# Sheet1.net
KiCad netlist of a schematic drawn in Altium Designer
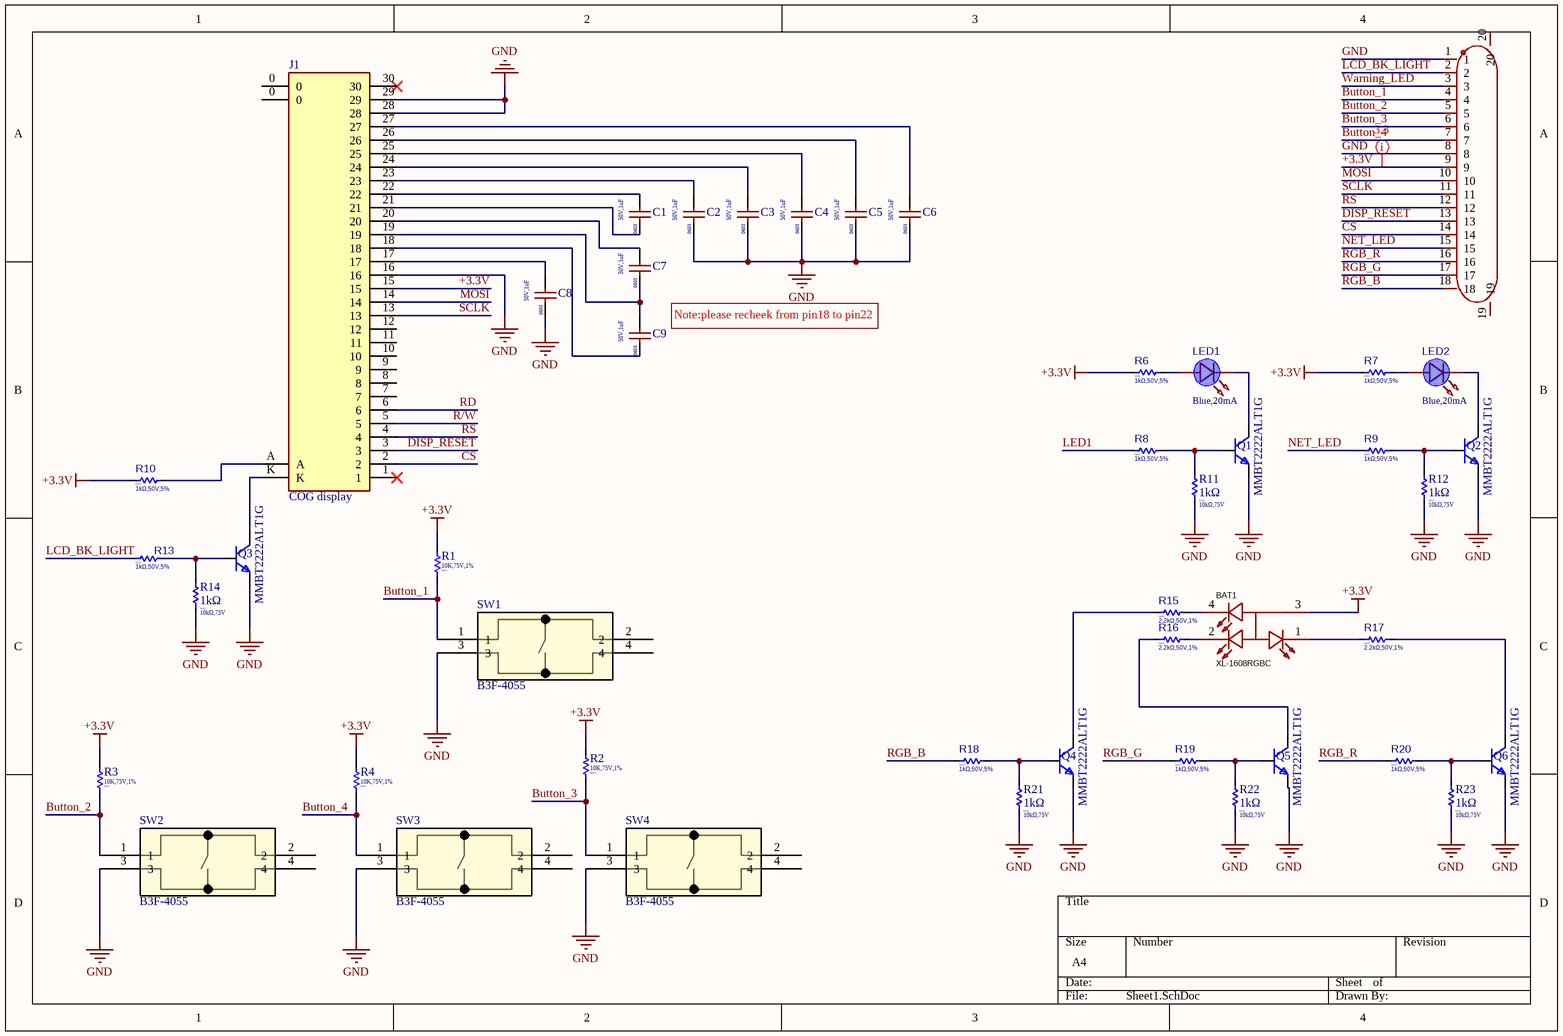
[diagram p0: Sheet1.SchDoc]

(export (version "E")
  (design (tool "Eeschema 10.0.6"))
  (components
    (comp (ref "BAT1")
      (value "XL-1608RGBC")
      (footprint "LED RGB 0603")
      (description "0603 RGB LEDs ROHS")
      (fields (field (name "MANUFACTURER") "XINGLIGHT"))
      (libsource (lib "LED") (part "XL-1608RGBC"))
    )
    (comp (ref "C1")
      (value "50V,1uF")
      (footprint "C0603")
      (description "50V 1uF X7R ±10% 0603 Multilayer Ceramic Capacitors MLCC - SMD/SMT ROHS")
      (fields
        (field (name "MANUFACTURER") "FH")
        (field (name "MPN") "0603B105K500NT")
        (field (name "PACKAGE") "0603")
      )
      (libsource (lib "RCL") (part "0603B105K500NT"))
    )
    (comp (ref "C2")
      (value "50V,1uF")
      (footprint "C0603")
      (description "50V 1uF X7R ±10% 0603 Multilayer Ceramic Capacitors MLCC - SMD/SMT ROHS")
      (fields
        (field (name "MANUFACTURER") "FH")
        (field (name "MPN") "0603B105K500NT")
        (field (name "PACKAGE") "0603")
      )
      (libsource (lib "RCL") (part "0603B105K500NT"))
    )
    (comp (ref "C3")
      (value "50V,1uF")
      (footprint "C0603")
      (description "50V 1uF X7R ±10% 0603 Multilayer Ceramic Capacitors MLCC - SMD/SMT ROHS")
      (fields
        (field (name "MANUFACTURER") "FH")
        (field (name "MPN") "0603B105K500NT")
        (field (name "PACKAGE") "0603")
      )
      (libsource (lib "RCL") (part "0603B105K500NT"))
    )
    (comp (ref "C4")
      (value "50V,1uF")
      (footprint "C0603")
      (description "50V 1uF X7R ±10% 0603 Multilayer Ceramic Capacitors MLCC - SMD/SMT ROHS")
      (fields
        (field (name "MANUFACTURER") "FH")
        (field (name "MPN") "0603B105K500NT")
        (field (name "PACKAGE") "0603")
      )
      (libsource (lib "RCL") (part "0603B105K500NT"))
    )
    (comp (ref "C5")
      (value "50V,1uF")
      (footprint "C0603")
      (description "50V 1uF X7R ±10% 0603 Multilayer Ceramic Capacitors MLCC - SMD/SMT ROHS")
      (fields
        (field (name "MANUFACTURER") "FH")
        (field (name "MPN") "0603B105K500NT")
        (field (name "PACKAGE") "0603")
      )
      (libsource (lib "RCL") (part "0603B105K500NT"))
    )
    (comp (ref "C6")
      (value "50V,1uF")
      (footprint "C0603")
      (description "50V 1uF X7R ±10% 0603 Multilayer Ceramic Capacitors MLCC - SMD/SMT ROHS")
      (fields
        (field (name "MANUFACTURER") "FH")
        (field (name "MPN") "0603B105K500NT")
        (field (name "PACKAGE") "0603")
      )
      (libsource (lib "RCL") (part "0603B105K500NT"))
    )
    (comp (ref "C7")
      (value "50V,1uF")
      (footprint "C0603")
      (description "50V 1uF X7R ±10% 0603 Multilayer Ceramic Capacitors MLCC - SMD/SMT ROHS")
      (fields
        (field (name "MANUFACTURER") "FH")
        (field (name "MPN") "0603B105K500NT")
        (field (name "PACKAGE") "0603")
      )
      (libsource (lib "RCL") (part "0603B105K500NT"))
    )
    (comp (ref "C8")
      (value "50V,1uF")
      (footprint "C0603")
      (description "50V 1uF X7R ±10% 0603 Multilayer Ceramic Capacitors MLCC - SMD/SMT ROHS")
      (fields
        (field (name "MANUFACTURER") "FH")
        (field (name "MPN") "0603B105K500NT")
        (field (name "PACKAGE") "0603")
      )
      (libsource (lib "RCL") (part "0603B105K500NT"))
    )
    (comp (ref "C9")
      (value "50V,1uF")
      (footprint "C0603")
      (description "50V 1uF X7R ±10% 0603 Multilayer Ceramic Capacitors MLCC - SMD/SMT ROHS")
      (fields
        (field (name "MANUFACTURER") "FH")
        (field (name "MPN") "0603B105K500NT")
        (field (name "PACKAGE") "0603")
      )
      (libsource (lib "RCL") (part "0603B105K500NT"))
    )
    (comp (ref "FPC1")
      (value "FPC-05F-18PH20")
      (footprint "FPC-SMD_18P-P0.50_horizontal")
      (fields (field (name "MANUFACTURER") "XUNPU"))
      (libsource (lib "connector_button") (part "FPC-05F-18PH20"))
    )
    (comp (ref "J1")
      (value "COG display")
      (footprint "COG")
      (description "FPC CONNECTOR")
      (fields (field (name "MANUFACTURER") "XFCN"))
      (libsource (lib "Display") (part "COG display"))
    )
    (comp (ref "LED1")
      (value "Blue,20mA")
      (footprint "LED 0402")
      (fields (field (name "MANUFACTURER") "TOGIALED") (field (name "MPN") "TJ-S1005CL4T5ALC6B-A5"))
      (libsource (lib "LED") (part "TJ-S1005CL4T5ALC6B-A5"))
    )
    (comp (ref "LED2")
      (value "Blue,20mA")
      (footprint "LED 0402")
      (fields (field (name "MANUFACTURER") "TOGIALED") (field (name "MPN") "TJ-S1005CL4T5ALC6B-A5"))
      (libsource (lib "LED") (part "TJ-S1005CL4T5ALC6B-A5"))
    )
    (comp (ref "Q1")
      (value "MMBT2222ALT1G")
      (footprint "SOT-23")
      (description "Bipolar (BJT) Transistor NPN 40 V 600 mA 300MHz 225 mW Surface Mount SOT-23-3 (TO-236)")
      (fields (field (name "MANUFACTURER") "ON Semiconductor"))
      (libsource (lib "MOS_TRAN") (part "MMBT2222ALT1G"))
    )
    (comp (ref "Q2")
      (value "MMBT2222ALT1G")
      (footprint "SOT-23")
      (description "Bipolar (BJT) Transistor NPN 40 V 600 mA 300MHz 225 mW Surface Mount SOT-23-3 (TO-236)")
      (fields (field (name "MANUFACTURER") "ON Semiconductor"))
      (libsource (lib "MOS_TRAN") (part "MMBT2222ALT1G"))
    )
    (comp (ref "Q3")
      (value "MMBT2222ALT1G")
      (footprint "SOT-23")
      (description "Bipolar (BJT) Transistor NPN 40 V 600 mA 300MHz 225 mW Surface Mount SOT-23-3 (TO-236)")
      (fields (field (name "MANUFACTURER") "ON Semiconductor"))
      (libsource (lib "MOS_TRAN") (part "MMBT2222ALT1G"))
    )
    (comp (ref "Q4")
      (value "MMBT2222ALT1G")
      (footprint "SOT-23")
      (description "Bipolar (BJT) Transistor NPN 40 V 600 mA 300MHz 225 mW Surface Mount SOT-23-3 (TO-236)")
      (fields (field (name "MANUFACTURER") "ON Semiconductor"))
      (libsource (lib "MOS_TRAN") (part "MMBT2222ALT1G"))
    )
    (comp (ref "Q5")
      (value "MMBT2222ALT1G")
      (footprint "SOT-23")
      (description "Bipolar (BJT) Transistor NPN 40 V 600 mA 300MHz 225 mW Surface Mount SOT-23-3 (TO-236)")
      (fields (field (name "MANUFACTURER") "ON Semiconductor"))
      (libsource (lib "MOS_TRAN") (part "MMBT2222ALT1G"))
    )
    (comp (ref "Q6")
      (value "MMBT2222ALT1G")
      (footprint "SOT-23")
      (description "Bipolar (BJT) Transistor NPN 40 V 600 mA 300MHz 225 mW Surface Mount SOT-23-3 (TO-236)")
      (fields (field (name "MANUFACTURER") "ON Semiconductor"))
      (libsource (lib "MOS_TRAN") (part "MMBT2222ALT1G"))
    )
    (comp (ref "R1")
      (value "10K,75V,1%")
      (footprint "R0603")
      (description "100mW Thick Film Resistors ±100ppm/℃ ±1% 10kΩ 0603 Chip Resistor - Surface Mount ROHS")
      (fields
        (field (name "MPN") "0603WAF1002T5E")
        (field (name "MANUFACTURER") "UNI-ROYAL(Uniroyal Elec)")
        (field (name "PACKAGE") "0603")
      )
      (libsource (lib "RCL") (part "0603WAF1002T5E"))
    )
    (comp (ref "R2")
      (value "10K,75V,1%")
      (footprint "R0603")
      (description "100mW Thick Film Resistors ±100ppm/℃ ±1% 10kΩ 0603 Chip Resistor - Surface Mount ROHS")
      (fields
        (field (name "MPN") "0603WAF1002T5E")
        (field (name "MANUFACTURER") "UNI-ROYAL(Uniroyal Elec)")
        (field (name "PACKAGE") "0603")
      )
      (libsource (lib "RCL") (part "0603WAF1002T5E"))
    )
    (comp (ref "R3")
      (value "10K,75V,1%")
      (footprint "R0603")
      (description "100mW Thick Film Resistors ±100ppm/℃ ±1% 10kΩ 0603 Chip Resistor - Surface Mount ROHS")
      (fields
        (field (name "MPN") "0603WAF1002T5E")
        (field (name "MANUFACTURER") "UNI-ROYAL(Uniroyal Elec)")
        (field (name "PACKAGE") "0603")
      )
      (libsource (lib "RCL") (part "0603WAF1002T5E"))
    )
    (comp (ref "R4")
      (value "10K,75V,1%")
      (footprint "R0603")
      (description "100mW Thick Film Resistors ±100ppm/℃ ±1% 10kΩ 0603 Chip Resistor - Surface Mount ROHS")
      (fields
        (field (name "MPN") "0603WAF1002T5E")
        (field (name "MANUFACTURER") "UNI-ROYAL(Uniroyal Elec)")
        (field (name "PACKAGE") "0603")
      )
      (libsource (lib "RCL") (part "0603WAF1002T5E"))
    )
    (comp (ref "R6")
      (value "1kΩ,50V,5%")
      (footprint "R0402")
      (description "125mW Thick Film Resistors 50V ±200ppm/℃ ±5% 1kΩ 0402 Chip Resistor - Surface Mount ROHS")
      (fields
        (field (name "MPN") "SR0402JR-7W1KL")
        (field (name "MANUFACTURER") "YAGEO")
        (field (name "PACKAGE") "0402")
      )
      (libsource (lib "RCL") (part "SR0402JR-7W1KL"))
    )
    (comp (ref "R7")
      (value "1kΩ,50V,5%")
      (footprint "R0402")
      (description "125mW Thick Film Resistors 50V ±200ppm/℃ ±5% 1kΩ 0402 Chip Resistor - Surface Mount ROHS")
      (fields
        (field (name "MPN") "SR0402JR-7W1KL")
        (field (name "MANUFACTURER") "YAGEO")
        (field (name "PACKAGE") "0402")
      )
      (libsource (lib "RCL") (part "SR0402JR-7W1KL"))
    )
    (comp (ref "R8")
      (value "1kΩ,50V,5%")
      (footprint "R0402")
      (description "125mW Thick Film Resistors 50V ±200ppm/℃ ±5% 1kΩ 0402 Chip Resistor - Surface Mount ROHS")
      (fields
        (field (name "MPN") "SR0402JR-7W1KL")
        (field (name "MANUFACTURER") "YAGEO")
        (field (name "PACKAGE") "0402")
      )
      (libsource (lib "RCL") (part "SR0402JR-7W1KL"))
    )
    (comp (ref "R9")
      (value "1kΩ,50V,5%")
      (footprint "R0402")
      (description "125mW Thick Film Resistors 50V ±200ppm/℃ ±5% 1kΩ 0402 Chip Resistor - Surface Mount ROHS")
      (fields
        (field (name "MPN") "SR0402JR-7W1KL")
        (field (name "MANUFACTURER") "YAGEO")
        (field (name "PACKAGE") "0402")
      )
      (libsource (lib "RCL") (part "SR0402JR-7W1KL"))
    )
    (comp (ref "R10")
      (value "1kΩ,50V,5%")
      (footprint "R0402")
      (description "125mW Thick Film Resistors 50V ±200ppm/℃ ±5% 1kΩ 0402 Chip Resistor - Surface Mount ROHS")
      (fields
        (field (name "MPN") "SR0402JR-7W1KL")
        (field (name "MANUFACTURER") "YAGEO")
        (field (name "PACKAGE") "0402")
      )
      (libsource (lib "RCL") (part "SR0402JR-7W1KL"))
    )
    (comp (ref "R11")
      (value "1kΩ")
      (footprint "R0402")
      (description "62.5mW Thick Film Resistors ±100ppm/℃ ±1% 1kΩ 0402 Chip Resistor - Surface Mount ROHS")
      (fields
        (field (name "MANUFACTURER") "UNI-ROYAL(Uniroyal Elec)")
        (field (name "MPN") "0603WAF1002T5E")
        (field (name "PACKAGE") "0402")
        (field (name "ALTIUM_VALUE") "10kΩ,75V")
      )
      (libsource (lib "RCL") (part "0402WGF1001TCE"))
    )
    (comp (ref "R12")
      (value "1kΩ")
      (footprint "R0402")
      (description "62.5mW Thick Film Resistors ±100ppm/℃ ±1% 1kΩ 0402 Chip Resistor - Surface Mount ROHS")
      (fields
        (field (name "MANUFACTURER") "UNI-ROYAL(Uniroyal Elec)")
        (field (name "MPN") "0603WAF1002T5E")
        (field (name "PACKAGE") "0402")
        (field (name "ALTIUM_VALUE") "10kΩ,75V")
      )
      (libsource (lib "RCL") (part "0402WGF1001TCE"))
    )
    (comp (ref "R13")
      (value "1kΩ,50V,5%")
      (footprint "R0402")
      (description "125mW Thick Film Resistors 50V ±200ppm/℃ ±5% 1kΩ 0402 Chip Resistor - Surface Mount ROHS")
      (fields
        (field (name "MPN") "SR0402JR-7W1KL")
        (field (name "MANUFACTURER") "YAGEO")
        (field (name "PACKAGE") "0402")
      )
      (libsource (lib "RCL") (part "SR0402JR-7W1KL"))
    )
    (comp (ref "R14")
      (value "1kΩ")
      (footprint "R0402")
      (description "62.5mW Thick Film Resistors ±100ppm/℃ ±1% 1kΩ 0402 Chip Resistor - Surface Mount ROHS")
      (fields
        (field (name "MANUFACTURER") "UNI-ROYAL(Uniroyal Elec)")
        (field (name "MPN") "0603WAF1002T5E")
        (field (name "PACKAGE") "0402")
        (field (name "ALTIUM_VALUE") "10kΩ,75V")
      )
      (libsource (lib "RCL") (part "0402WGF1001TCE"))
    )
    (comp (ref "R15")
      (value "2.2kΩ,50V,1%")
      (footprint "R0402")
      (description "62.5mW Thick Film Resistors 50V ±100ppm/℃ ±1% 2.2kΩ 0402 Chip Resistor - Surface Mount ROHS")
      (fields
        (field (name "MPN") "RC0402FR-072K2L")
        (field (name "MANUFACTURER") "YAGEO")
        (field (name "PACKAGE") "0402")
      )
      (libsource (lib "RCL") (part "RC0402FR-072K2L"))
    )
    (comp (ref "R16")
      (value "2.2kΩ,50V,1%")
      (footprint "R0402")
      (description "62.5mW Thick Film Resistors 50V ±100ppm/℃ ±1% 2.2kΩ 0402 Chip Resistor - Surface Mount ROHS")
      (fields
        (field (name "MPN") "RC0402FR-072K2L")
        (field (name "MANUFACTURER") "YAGEO")
        (field (name "PACKAGE") "0402")
      )
      (libsource (lib "RCL") (part "RC0402FR-072K2L"))
    )
    (comp (ref "R17")
      (value "2.2kΩ,50V,1%")
      (footprint "R0402")
      (description "62.5mW Thick Film Resistors 50V ±100ppm/℃ ±1% 2.2kΩ 0402 Chip Resistor - Surface Mount ROHS")
      (fields
        (field (name "MPN") "RC0402FR-072K2L")
        (field (name "MANUFACTURER") "YAGEO")
        (field (name "PACKAGE") "0402")
      )
      (libsource (lib "RCL") (part "RC0402FR-072K2L"))
    )
    (comp (ref "R18")
      (value "1kΩ,50V,5%")
      (footprint "R0402")
      (description "125mW Thick Film Resistors 50V ±200ppm/℃ ±5% 1kΩ 0402 Chip Resistor - Surface Mount ROHS")
      (fields
        (field (name "MPN") "SR0402JR-7W1KL")
        (field (name "MANUFACTURER") "YAGEO")
        (field (name "PACKAGE") "0402")
      )
      (libsource (lib "RCL") (part "SR0402JR-7W1KL"))
    )
    (comp (ref "R19")
      (value "1kΩ,50V,5%")
      (footprint "R0402")
      (description "125mW Thick Film Resistors 50V ±200ppm/℃ ±5% 1kΩ 0402 Chip Resistor - Surface Mount ROHS")
      (fields
        (field (name "MPN") "SR0402JR-7W1KL")
        (field (name "MANUFACTURER") "YAGEO")
        (field (name "PACKAGE") "0402")
      )
      (libsource (lib "RCL") (part "SR0402JR-7W1KL"))
    )
    (comp (ref "R20")
      (value "1kΩ,50V,5%")
      (footprint "R0402")
      (description "125mW Thick Film Resistors 50V ±200ppm/℃ ±5% 1kΩ 0402 Chip Resistor - Surface Mount ROHS")
      (fields
        (field (name "MPN") "SR0402JR-7W1KL")
        (field (name "MANUFACTURER") "YAGEO")
        (field (name "PACKAGE") "0402")
      )
      (libsource (lib "RCL") (part "SR0402JR-7W1KL"))
    )
    (comp (ref "R21")
      (value "1kΩ")
      (footprint "R0402")
      (description "62.5mW Thick Film Resistors ±100ppm/℃ ±1% 1kΩ 0402 Chip Resistor - Surface Mount ROHS")
      (fields
        (field (name "MANUFACTURER") "UNI-ROYAL(Uniroyal Elec)")
        (field (name "MPN") "0603WAF1002T5E")
        (field (name "PACKAGE") "0402")
        (field (name "ALTIUM_VALUE") "10kΩ,75V")
      )
      (libsource (lib "RCL") (part "0402WGF1001TCE"))
    )
    (comp (ref "R22")
      (value "1kΩ")
      (footprint "R0402")
      (description "62.5mW Thick Film Resistors ±100ppm/℃ ±1% 1kΩ 0402 Chip Resistor - Surface Mount ROHS")
      (fields
        (field (name "MANUFACTURER") "UNI-ROYAL(Uniroyal Elec)")
        (field (name "MPN") "0603WAF1002T5E")
        (field (name "PACKAGE") "0402")
        (field (name "ALTIUM_VALUE") "10kΩ,75V")
      )
      (libsource (lib "RCL") (part "0402WGF1001TCE"))
    )
    (comp (ref "R23")
      (value "1kΩ")
      (footprint "R0402")
      (description "62.5mW Thick Film Resistors ±100ppm/℃ ±1% 1kΩ 0402 Chip Resistor - Surface Mount ROHS")
      (fields
        (field (name "MANUFACTURER") "UNI-ROYAL(Uniroyal Elec)")
        (field (name "MPN") "0603WAF1002T5E")
        (field (name "PACKAGE") "0402")
        (field (name "ALTIUM_VALUE") "10kΩ,75V")
      )
      (libsource (lib "RCL") (part "0402WGF1001TCE"))
    )
    (comp (ref "SW1")
      (value "B3F-4055")
      (footprint "SW_B3F-4050_OMR")
      (description "Tactile Switch SPST-NO Top Actuated Through Hole")
      (libsource (lib "connector_button") (part "B3F-4055"))
    )
    (comp (ref "SW2")
      (value "B3F-4055")
      (footprint "SW_B3F-4050_OMR")
      (description "Tactile Switch SPST-NO Top Actuated Through Hole")
      (libsource (lib "connector_button") (part "B3F-4055"))
    )
    (comp (ref "SW3")
      (value "B3F-4055")
      (footprint "SW_B3F-4050_OMR")
      (description "Tactile Switch SPST-NO Top Actuated Through Hole")
      (libsource (lib "connector_button") (part "B3F-4055"))
    )
    (comp (ref "SW4")
      (value "B3F-4055")
      (footprint "SW_B3F-4050_OMR")
      (description "Tactile Switch SPST-NO Top Actuated Through Hole")
      (libsource (lib "connector_button") (part "B3F-4055"))
    )
  )
  (nets
    (net (code "1") (name "+3.3V") (class "Default")
      (node (ref "BAT1") (pin "3") (pinfunction "com_3") (pintype "passive"))
      (node (ref "FPC1") (pin "9") (pinfunction "9_9") (pintype "passive"))
      (node (ref "J1") (pin "15") (pinfunction "15_15") (pintype "passive"))
      (node (ref "R1") (pin "2") (pinfunction "2_2") (pintype "passive"))
      (node (ref "R10") (pin "1") (pinfunction "1_1") (pintype "passive"))
      (node (ref "R2") (pin "2") (pinfunction "2_2") (pintype "passive"))
      (node (ref "R3") (pin "2") (pinfunction "2_2") (pintype "passive"))
      (node (ref "R4") (pin "2") (pinfunction "2_2") (pintype "passive"))
      (node (ref "R6") (pin "1") (pinfunction "1_1") (pintype "passive"))
      (node (ref "R7") (pin "1") (pinfunction "1_1") (pintype "passive"))
    )
    (net (code "2") (name "/Button_1") (class "Default")
      (node (ref "FPC1") (pin "4") (pinfunction "4_4") (pintype "passive"))
      (node (ref "R1") (pin "1") (pinfunction "1_1") (pintype "passive"))
      (node (ref "SW1") (pin "1") (pinfunction "1_1") (pintype "passive"))
    )
    (net (code "3") (name "/Button_2") (class "Default")
      (node (ref "FPC1") (pin "5") (pinfunction "5_5") (pintype "passive"))
      (node (ref "R3") (pin "1") (pinfunction "1_1") (pintype "passive"))
      (node (ref "SW2") (pin "1") (pinfunction "1_1") (pintype "passive"))
    )
    (net (code "4") (name "/Button_3") (class "Default")
      (node (ref "FPC1") (pin "6") (pinfunction "6_6") (pintype "passive"))
      (node (ref "R2") (pin "1") (pinfunction "1_1") (pintype "passive"))
      (node (ref "SW4") (pin "1") (pinfunction "1_1") (pintype "passive"))
    )
    (net (code "5") (name "/Button_4") (class "Default")
      (node (ref "FPC1") (pin "7") (pinfunction "7_7") (pintype "passive"))
      (node (ref "R4") (pin "1") (pinfunction "1_1") (pintype "passive"))
      (node (ref "SW3") (pin "1") (pinfunction "1_1") (pintype "passive"))
    )
    (net (code "6") (name "/CS") (class "Default")
      (node (ref "FPC1") (pin "14") (pinfunction "14_14") (pintype "passive"))
      (node (ref "J1") (pin "2") (pinfunction "2_2") (pintype "passive"))
    )
    (net (code "7") (name "/DISP_RESET") (class "Default")
      (node (ref "FPC1") (pin "13") (pinfunction "13_13") (pintype "passive"))
      (node (ref "J1") (pin "3") (pinfunction "3_3") (pintype "passive"))
    )
    (net (code "8") (name "/LCD_BK_LIGHT") (class "Default")
      (node (ref "FPC1") (pin "2") (pinfunction "2_2") (pintype "passive"))
      (node (ref "R13") (pin "1") (pinfunction "1_1") (pintype "passive"))
    )
    (net (code "9") (name "/LED1") (class "Default")
      (node (ref "R8") (pin "1") (pinfunction "1_1") (pintype "passive"))
    )
    (net (code "10") (name "/MOSI") (class "Default")
      (node (ref "FPC1") (pin "10") (pinfunction "10_10") (pintype "passive"))
      (node (ref "J1") (pin "14") (pinfunction "14_14") (pintype "passive"))
    )
    (net (code "11") (name "/NET_LED") (class "Default")
      (node (ref "FPC1") (pin "15") (pinfunction "15_15") (pintype "passive"))
      (node (ref "R9") (pin "1") (pinfunction "1_1") (pintype "passive"))
    )
    (net (code "12") (name "/RD") (class "Default")
      (node (ref "J1") (pin "6") (pinfunction "6_6") (pintype "passive"))
    )
    (net (code "13") (name "/RGB_B") (class "Default")
      (node (ref "FPC1") (pin "18") (pinfunction "18_18") (pintype "passive"))
      (node (ref "R18") (pin "1") (pinfunction "1_1") (pintype "passive"))
    )
    (net (code "14") (name "/RGB_G") (class "Default")
      (node (ref "FPC1") (pin "17") (pinfunction "17_17") (pintype "passive"))
      (node (ref "R19") (pin "1") (pinfunction "1_1") (pintype "passive"))
    )
    (net (code "15") (name "/RGB_R") (class "Default")
      (node (ref "FPC1") (pin "16") (pinfunction "16_16") (pintype "passive"))
      (node (ref "R20") (pin "1") (pinfunction "1_1") (pintype "passive"))
    )
    (net (code "16") (name "/RS") (class "Default")
      (node (ref "FPC1") (pin "12") (pinfunction "12_12") (pintype "passive"))
      (node (ref "J1") (pin "4") (pinfunction "4_4") (pintype "passive"))
    )
    (net (code "17") (name "/R{slash}W") (class "Default")
      (node (ref "J1") (pin "5") (pinfunction "5_5") (pintype "passive"))
    )
    (net (code "18") (name "/SCLK") (class "Default")
      (node (ref "FPC1") (pin "11") (pinfunction "11_11") (pintype "passive"))
      (node (ref "J1") (pin "13") (pinfunction "13_13") (pintype "passive"))
    )
    (net (code "19") (name "/Warning_LED") (class "Default")
      (node (ref "FPC1") (pin "3") (pinfunction "3_3") (pintype "passive"))
    )
    (net (code "20") (name "GND") (class "Default")
      (node (ref "C2") (pin "1") (pinfunction "1_1") (pintype "passive"))
      (node (ref "C3") (pin "1") (pinfunction "1_1") (pintype "passive"))
      (node (ref "C4") (pin "1") (pinfunction "1_1") (pintype "passive"))
      (node (ref "C5") (pin "1") (pinfunction "1_1") (pintype "passive"))
      (node (ref "C6") (pin "1") (pinfunction "1_1") (pintype "passive"))
      (node (ref "C8") (pin "1") (pinfunction "1_1") (pintype "passive"))
      (node (ref "FPC1") (pin "1") (pinfunction "1_1") (pintype "passive"))
      (node (ref "FPC1") (pin "8") (pinfunction "8_8") (pintype "passive"))
      (node (ref "J1") (pin "16") (pinfunction "16_16") (pintype "passive"))
      (node (ref "J1") (pin "28") (pinfunction "28_28") (pintype "passive"))
      (node (ref "J1") (pin "29") (pinfunction "29_29") (pintype "passive"))
      (node (ref "Q1") (pin "2") (pinfunction "2_2") (pintype "passive"))
      (node (ref "Q2") (pin "2") (pinfunction "2_2") (pintype "passive"))
      (node (ref "Q3") (pin "2") (pinfunction "2_2") (pintype "passive"))
      (node (ref "Q4") (pin "2") (pinfunction "2_2") (pintype "passive"))
      (node (ref "Q5") (pin "2") (pinfunction "2_2") (pintype "passive"))
      (node (ref "Q6") (pin "2") (pinfunction "2_2") (pintype "passive"))
      (node (ref "R11") (pin "1") (pinfunction "1_1") (pintype "passive"))
      (node (ref "R12") (pin "1") (pinfunction "1_1") (pintype "passive"))
      (node (ref "R14") (pin "1") (pinfunction "1_1") (pintype "passive"))
      (node (ref "R21") (pin "1") (pinfunction "1_1") (pintype "passive"))
      (node (ref "R22") (pin "1") (pinfunction "1_1") (pintype "passive"))
      (node (ref "R23") (pin "1") (pinfunction "1_1") (pintype "passive"))
      (node (ref "SW1") (pin "3") (pinfunction "3_3") (pintype "passive"))
      (node (ref "SW2") (pin "3") (pinfunction "3_3") (pintype "passive"))
      (node (ref "SW3") (pin "3") (pinfunction "3_3") (pintype "passive"))
      (node (ref "SW4") (pin "3") (pinfunction "3_3") (pintype "passive"))
    )
    (net (code "21") (name "Net-(BAT1-Pad1)") (class "Default")
      (node (ref "BAT1") (pin "1") (pinfunction "1_1") (pintype "passive"))
      (node (ref "R17") (pin "1") (pinfunction "1_1") (pintype "passive"))
    )
    (net (code "22") (name "Net-(BAT1-Pad2)") (class "Default")
      (node (ref "BAT1") (pin "2") (pinfunction "2_2") (pintype "passive"))
      (node (ref "R16") (pin "1") (pinfunction "1_1") (pintype "passive"))
    )
    (net (code "23") (name "Net-(BAT1-Pad4)") (class "Default")
      (node (ref "BAT1") (pin "4") (pinfunction "4_4") (pintype "passive"))
      (node (ref "R15") (pin "1") (pinfunction "1_1") (pintype "passive"))
    )
    (net (code "24") (name "Net-(C1-Pad1)") (class "Default")
      (node (ref "C1") (pin "1") (pinfunction "1_1") (pintype "passive"))
      (node (ref "J1") (pin "21") (pinfunction "21_21") (pintype "passive"))
    )
    (net (code "25") (name "Net-(C1-Pad2)") (class "Default")
      (node (ref "C1") (pin "2") (pinfunction "2_2") (pintype "passive"))
      (node (ref "J1") (pin "22") (pinfunction "22_22") (pintype "passive"))
    )
    (net (code "26") (name "Net-(C2-Pad2)") (class "Default")
      (node (ref "C2") (pin "2") (pinfunction "2_2") (pintype "passive"))
      (node (ref "J1") (pin "23") (pinfunction "23_23") (pintype "passive"))
    )
    (net (code "27") (name "Net-(C3-Pad2)") (class "Default")
      (node (ref "C3") (pin "2") (pinfunction "2_2") (pintype "passive"))
      (node (ref "J1") (pin "24") (pinfunction "24_24") (pintype "passive"))
    )
    (net (code "28") (name "Net-(C4-Pad2)") (class "Default")
      (node (ref "C4") (pin "2") (pinfunction "2_2") (pintype "passive"))
      (node (ref "J1") (pin "25") (pinfunction "25_25") (pintype "passive"))
    )
    (net (code "29") (name "Net-(C5-Pad2)") (class "Default")
      (node (ref "C5") (pin "2") (pinfunction "2_2") (pintype "passive"))
      (node (ref "J1") (pin "26") (pinfunction "26_26") (pintype "passive"))
    )
    (net (code "30") (name "Net-(C6-Pad2)") (class "Default")
      (node (ref "C6") (pin "2") (pinfunction "2_2") (pintype "passive"))
      (node (ref "J1") (pin "27") (pinfunction "27_27") (pintype "passive"))
    )
    (net (code "31") (name "Net-(C7-Pad1)") (class "Default")
      (node (ref "C7") (pin "1") (pinfunction "1_1") (pintype "passive"))
      (node (ref "C9") (pin "2") (pinfunction "2_2") (pintype "passive"))
      (node (ref "J1") (pin "19") (pinfunction "19_19") (pintype "passive"))
    )
    (net (code "32") (name "Net-(C7-Pad2)") (class "Default")
      (node (ref "C7") (pin "2") (pinfunction "2_2") (pintype "passive"))
      (node (ref "J1") (pin "20") (pinfunction "20_20") (pintype "passive"))
    )
    (net (code "33") (name "Net-(C8-Pad2)") (class "Default")
      (node (ref "C8") (pin "2") (pinfunction "2_2") (pintype "passive"))
      (node (ref "J1") (pin "17") (pinfunction "17_17") (pintype "passive"))
    )
    (net (code "34") (name "Net-(C9-Pad1)") (class "Default")
      (node (ref "C9") (pin "1") (pinfunction "1_1") (pintype "passive"))
      (node (ref "J1") (pin "18") (pinfunction "18_18") (pintype "passive"))
    )
    (net (code "35") (name "Net-(J1-PadA)") (class "Default")
      (node (ref "J1") (pin "A") (pinfunction "A_A") (pintype "passive"))
      (node (ref "R10") (pin "2") (pinfunction "2_2") (pintype "passive"))
    )
    (net (code "36") (name "Net-(J1-PadK)") (class "Default")
      (node (ref "J1") (pin "K") (pinfunction "K_K") (pintype "passive"))
      (node (ref "Q3") (pin "3") (pinfunction "3_3") (pintype "passive"))
    )
    (net (code "37") (name "Net-(LED1-A)") (class "Default")
      (node (ref "LED1") (pin "2") (pinfunction "A_2") (pintype "passive"))
      (node (ref "R6") (pin "2") (pinfunction "2_2") (pintype "passive"))
    )
    (net (code "38") (name "Net-(LED1-K)") (class "Default")
      (node (ref "LED1") (pin "1") (pinfunction "K_1") (pintype "passive"))
      (node (ref "Q1") (pin "3") (pinfunction "3_3") (pintype "passive"))
    )
    (net (code "39") (name "Net-(LED2-A)") (class "Default")
      (node (ref "LED2") (pin "2") (pinfunction "A_2") (pintype "passive"))
      (node (ref "R7") (pin "2") (pinfunction "2_2") (pintype "passive"))
    )
    (net (code "40") (name "Net-(LED2-K)") (class "Default")
      (node (ref "LED2") (pin "1") (pinfunction "K_1") (pintype "passive"))
      (node (ref "Q2") (pin "3") (pinfunction "3_3") (pintype "passive"))
    )
    (net (code "41") (name "Net-(Q1-Pad1)") (class "Default")
      (node (ref "Q1") (pin "1") (pinfunction "1_1") (pintype "passive"))
      (node (ref "R11") (pin "2") (pinfunction "2_2") (pintype "passive"))
      (node (ref "R8") (pin "2") (pinfunction "2_2") (pintype "passive"))
    )
    (net (code "42") (name "Net-(Q2-Pad1)") (class "Default")
      (node (ref "Q2") (pin "1") (pinfunction "1_1") (pintype "passive"))
      (node (ref "R12") (pin "2") (pinfunction "2_2") (pintype "passive"))
      (node (ref "R9") (pin "2") (pinfunction "2_2") (pintype "passive"))
    )
    (net (code "43") (name "Net-(Q3-Pad1)") (class "Default")
      (node (ref "Q3") (pin "1") (pinfunction "1_1") (pintype "passive"))
      (node (ref "R13") (pin "2") (pinfunction "2_2") (pintype "passive"))
      (node (ref "R14") (pin "2") (pinfunction "2_2") (pintype "passive"))
    )
    (net (code "44") (name "Net-(Q4-Pad1)") (class "Default")
      (node (ref "Q4") (pin "1") (pinfunction "1_1") (pintype "passive"))
      (node (ref "R18") (pin "2") (pinfunction "2_2") (pintype "passive"))
      (node (ref "R21") (pin "2") (pinfunction "2_2") (pintype "passive"))
    )
    (net (code "45") (name "Net-(Q4-Pad3)") (class "Default")
      (node (ref "Q4") (pin "3") (pinfunction "3_3") (pintype "passive"))
      (node (ref "R15") (pin "2") (pinfunction "2_2") (pintype "passive"))
    )
    (net (code "46") (name "Net-(Q5-Pad1)") (class "Default")
      (node (ref "Q5") (pin "1") (pinfunction "1_1") (pintype "passive"))
      (node (ref "R19") (pin "2") (pinfunction "2_2") (pintype "passive"))
      (node (ref "R22") (pin "2") (pinfunction "2_2") (pintype "passive"))
    )
    (net (code "47") (name "Net-(Q5-Pad3)") (class "Default")
      (node (ref "Q5") (pin "3") (pinfunction "3_3") (pintype "passive"))
      (node (ref "R16") (pin "2") (pinfunction "2_2") (pintype "passive"))
    )
    (net (code "48") (name "Net-(Q6-Pad1)") (class "Default")
      (node (ref "Q6") (pin "1") (pinfunction "1_1") (pintype "passive"))
      (node (ref "R20") (pin "2") (pinfunction "2_2") (pintype "passive"))
      (node (ref "R23") (pin "2") (pinfunction "2_2") (pintype "passive"))
    )
    (net (code "49") (name "Net-(Q6-Pad3)") (class "Default")
      (node (ref "Q6") (pin "3") (pinfunction "3_3") (pintype "passive"))
      (node (ref "R17") (pin "2") (pinfunction "2_2") (pintype "passive"))
    )
    (net (code "50") (name "unconnected-(FPC1-Pad19)") (class "Default")
      (node (ref "FPC1") (pin "19") (pinfunction "19_19") (pintype "passive"))
    )
    (net (code "51") (name "unconnected-(FPC1-Pad20)") (class "Default")
      (node (ref "FPC1") (pin "20") (pinfunction "20_20") (pintype "passive"))
    )
    (net (code "52") (name "unconnected-(J1-Pad0)") (class "Default")
      (node (ref "J1") (pin "0") (pinfunction "0_0") (pintype "passive"))
    )
    (net (code "53") (name "unconnected-(J1-Pad0)_1") (class "Default")
      (node (ref "J1") (pin "0") (pinfunction "0_0") (pintype "passive"))
    )
    (net (code "54") (name "unconnected-(J1-Pad1)") (class "Default")
      (node (ref "J1") (pin "1") (pinfunction "1_1") (pintype "passive+no_connect"))
    )
    (net (code "55") (name "unconnected-(J1-Pad7)") (class "Default")
      (node (ref "J1") (pin "7") (pinfunction "7_7") (pintype "passive"))
    )
    (net (code "56") (name "unconnected-(J1-Pad8)") (class "Default")
      (node (ref "J1") (pin "8") (pinfunction "8_8") (pintype "passive"))
    )
    (net (code "57") (name "unconnected-(J1-Pad9)") (class "Default")
      (node (ref "J1") (pin "9") (pinfunction "9_9") (pintype "passive"))
    )
    (net (code "58") (name "unconnected-(J1-Pad10)") (class "Default")
      (node (ref "J1") (pin "10") (pinfunction "10_10") (pintype "passive"))
    )
    (net (code "59") (name "unconnected-(J1-Pad11)") (class "Default")
      (node (ref "J1") (pin "11") (pinfunction "11_11") (pintype "passive"))
    )
    (net (code "60") (name "unconnected-(J1-Pad12)") (class "Default")
      (node (ref "J1") (pin "12") (pinfunction "12_12") (pintype "passive"))
    )
    (net (code "61") (name "unconnected-(J1-Pad30)") (class "Default")
      (node (ref "J1") (pin "30") (pinfunction "30_30") (pintype "passive+no_connect"))
    )
    (net (code "62") (name "unconnected-(SW1-Pad2)") (class "Default")
      (node (ref "SW1") (pin "2") (pinfunction "2_2") (pintype "passive"))
    )
    (net (code "63") (name "unconnected-(SW1-Pad4)") (class "Default")
      (node (ref "SW1") (pin "4") (pinfunction "4_4") (pintype "passive"))
    )
    (net (code "64") (name "unconnected-(SW2-Pad2)") (class "Default")
      (node (ref "SW2") (pin "2") (pinfunction "2_2") (pintype "passive"))
    )
    (net (code "65") (name "unconnected-(SW2-Pad4)") (class "Default")
      (node (ref "SW2") (pin "4") (pinfunction "4_4") (pintype "passive"))
    )
    (net (code "66") (name "unconnected-(SW3-Pad2)") (class "Default")
      (node (ref "SW3") (pin "2") (pinfunction "2_2") (pintype "passive"))
    )
    (net (code "67") (name "unconnected-(SW3-Pad4)") (class "Default")
      (node (ref "SW3") (pin "4") (pinfunction "4_4") (pintype "passive"))
    )
    (net (code "68") (name "unconnected-(SW4-Pad2)") (class "Default")
      (node (ref "SW4") (pin "2") (pinfunction "2_2") (pintype "passive"))
    )
    (net (code "69") (name "unconnected-(SW4-Pad4)") (class "Default")
      (node (ref "SW4") (pin "4") (pinfunction "4_4") (pintype "passive"))
    )
  )
)
